# ProgSwitch.net
KiCad netlist of a schematic drawn in EAGLE
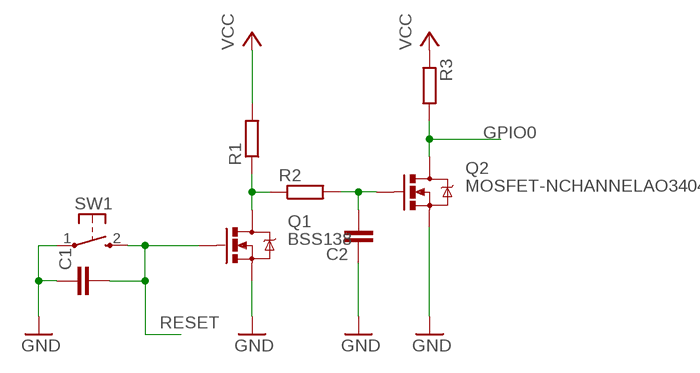
[diagram p0: schematic, sheet 1]

(export (version "E")
  (design (tool "Eeschema 10.0.6"))
  (components
    (comp (ref "C1")
      (value "C-EU025-024X044")
      (footprint "eagle-import:C025-024X044")
      (libsource (lib "eagle-import") (part "C-EU025-024X044"))
    )
    (comp (ref "C2")
      (value "C-EU025-024X044")
      (footprint "eagle-import:C025-024X044")
      (libsource (lib "eagle-import") (part "C-EU025-024X044"))
    )
    (comp (ref "Q1")
      (value "BSS138")
      (footprint "eagle-import:SOT23-3")
      (libsource (lib "eagle-import") (part "MOSFET-NCHANNELAO3404A"))
    )
    (comp (ref "Q2")
      (value "MOSFET-NCHANNELAO3404A")
      (footprint "eagle-import:SOT23-3")
      (libsource (lib "eagle-import") (part "MOSFET-NCHANNELAO3404A"))
    )
    (comp (ref "R1")
      (value "R-EU_0204/5")
      (footprint "eagle-import:0204_5")
      (libsource (lib "eagle-import") (part "R-EU_0204/5"))
    )
    (comp (ref "R2")
      (value "R-EU_0204/5")
      (footprint "eagle-import:0204_5")
      (libsource (lib "eagle-import") (part "R-EU_0204/5"))
    )
    (comp (ref "R3")
      (value "R-EU_0204/5")
      (footprint "eagle-import:0204_5")
      (libsource (lib "eagle-import") (part "R-EU_0204/5"))
    )
    (comp (ref "SW1")
      (value "KSS-2EG4430")
      (footprint "eagle-import:KSS-2EG4430")
      (libsource (lib "eagle-import") (part "KSS-2EG4430"))
    )
  )
  (nets
    (net (code "1") (name "/GPIO0") (class "Default")
      (node (ref "Q2") (pin "3") (pinfunction "D_3") (pintype "passive"))
      (node (ref "R3") (pin "2") (pinfunction "2_2") (pintype "passive"))
    )
    (net (code "2") (name "/RESET") (class "Default")
      (node (ref "C1") (pin "2") (pinfunction "2_2") (pintype "passive"))
      (node (ref "Q1") (pin "1") (pinfunction "G_1") (pintype "passive"))
      (node (ref "SW1") (pin "2") (pinfunction "S_2") (pintype "passive"))
    )
    (net (code "3") (name "GND") (class "Default")
      (node (ref "C1") (pin "1") (pinfunction "1_1") (pintype "passive"))
      (node (ref "C2") (pin "1") (pinfunction "1_1") (pintype "passive"))
      (node (ref "Q1") (pin "2") (pinfunction "S_2") (pintype "passive"))
      (node (ref "Q2") (pin "2") (pinfunction "S_2") (pintype "passive"))
      (node (ref "SW1") (pin "1") (pinfunction "P_1") (pintype "passive"))
    )
    (net (code "4") (name "Net-(Q1-D)") (class "Default")
      (node (ref "Q1") (pin "3") (pinfunction "D_3") (pintype "passive"))
      (node (ref "R1") (pin "1") (pinfunction "1_1") (pintype "passive"))
      (node (ref "R2") (pin "1") (pinfunction "1_1") (pintype "passive"))
    )
    (net (code "5") (name "Net-(Q2-G)") (class "Default")
      (node (ref "C2") (pin "2") (pinfunction "2_2") (pintype "passive"))
      (node (ref "Q2") (pin "1") (pinfunction "G_1") (pintype "passive"))
      (node (ref "R2") (pin "2") (pinfunction "2_2") (pintype "passive"))
    )
    (net (code "6") (name "VCC") (class "Default")
      (node (ref "R1") (pin "2") (pinfunction "2_2") (pintype "passive"))
      (node (ref "R3") (pin "1") (pinfunction "1_1") (pintype "passive"))
    )
  )
)
